# cSLIM-SA_RS485.net
KiCad netlist of a schematic drawn in Altium Designer
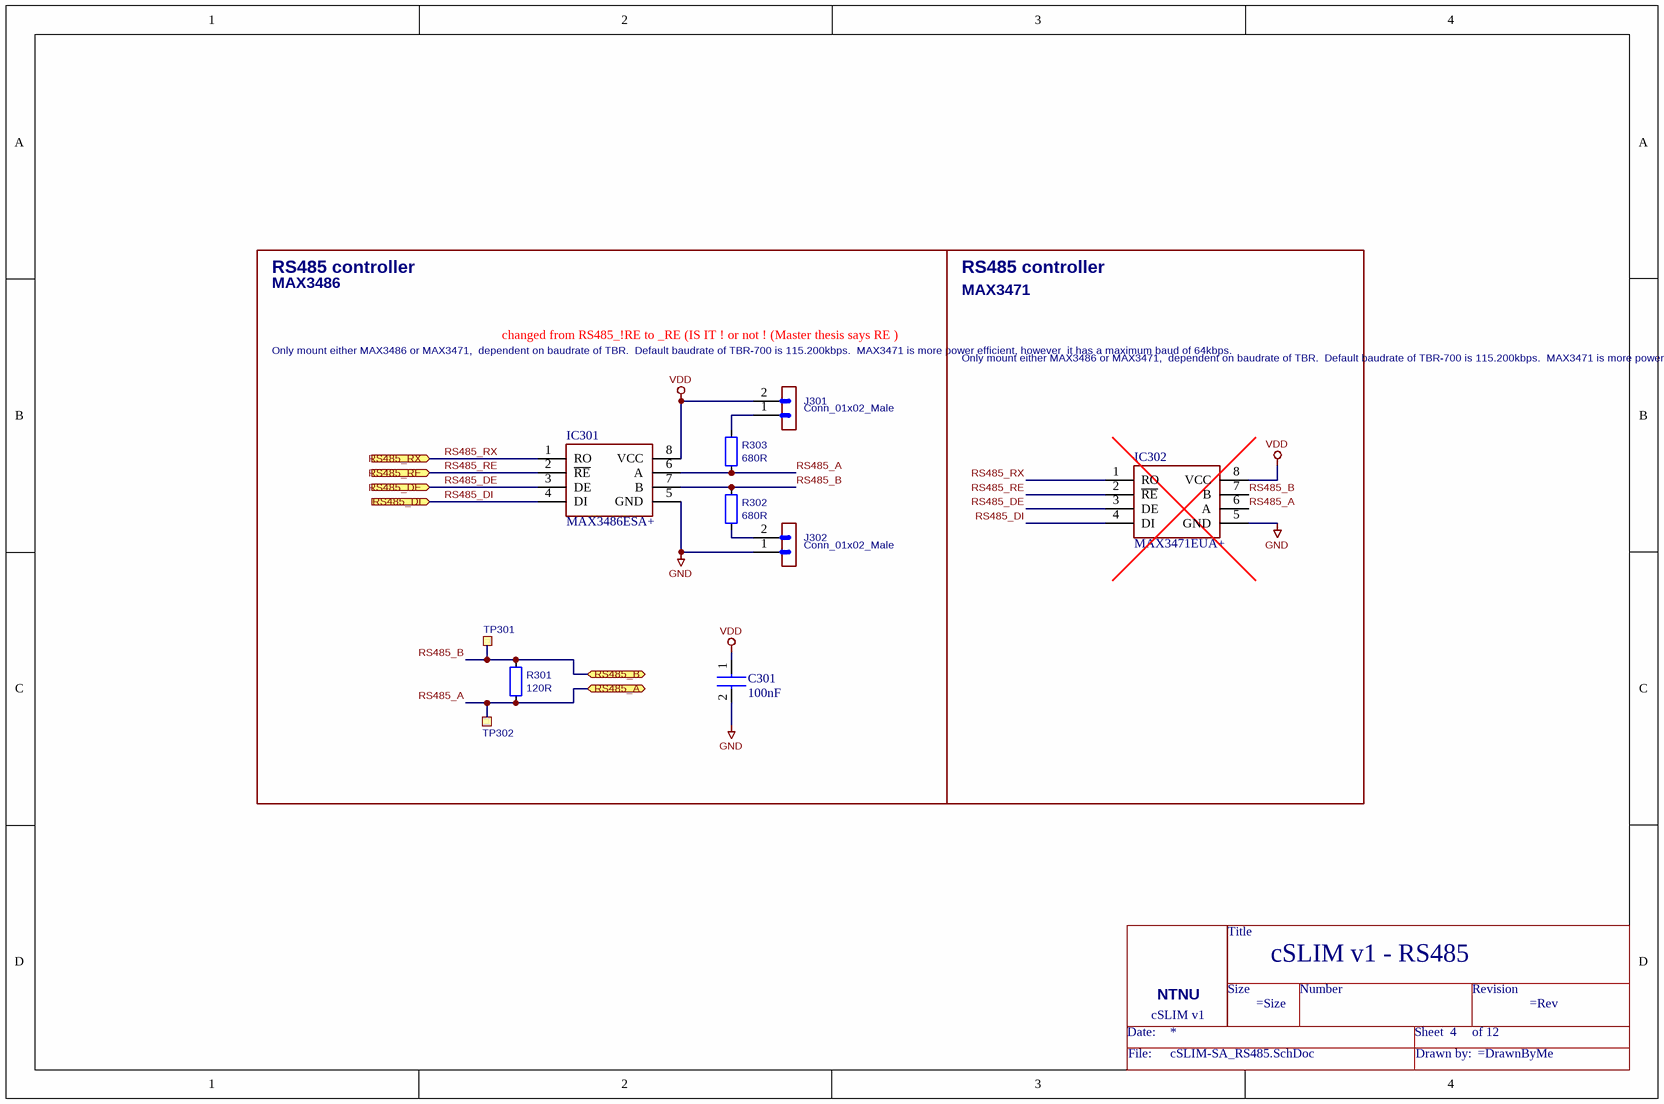
[diagram p0: cSLIM-SA_RS485.SchDoc]

(export (version "E")
  (design (tool "Eeschema 10.0.6"))
  (components
    (comp (ref "C301")
      (value "100nF")
      (footprint "cSLIM-SA:CAPC1608X90N")
      (description "Capacitor")
      (fields
        (field (name "MANUFACTURER_PART_NUMBER") "06033G104ZAT2A")
        (field (name "MOUSER PART NUMBER") "581-06033G104Z")
      )
      (libsource (lib "cSLIM-SA") (part "C"))
    )
    (comp (ref "IC301")
      (value "MAX3486ESA+")
      (footprint "cSLIM-SA:SOIC127P600X175-8N")
      (description "Integrated Circuit")
      (fields (field (name "MOUSER PART NUMBER") "700-MAX3486ESA"))
      (libsource (lib "cSLIM-SA") (part "MAX3486ESA+"))
    )
    (comp (ref "IC302")
      (value "MAX3471EUA+")
      (footprint "cSLIM-SA:SOP65P490X110-8N")
      (description "Integrated Circuit")
      (fields (field (name "MOUSER PART NUMBER") "700-MAX3471EUA"))
      (libsource (lib "cSLIM-SA") (part "MAX3471EUA+"))
    )
    (comp (ref "J301")
      (value "Conn_01x02_Male")
      (footprint "cSLIM-SA:HDRV2W110P0X254_1X2_508X254X854P")
      (description "Connector")
      (fields
        (field (name "MANUFACTURER_PART_NUMBER") "61300211121")
        (field (name "MOUSER PART NUMBER") "710-61300211121")
      )
      (libsource (lib "cSLIM-SA") (part "61300211121"))
    )
    (comp (ref "J302")
      (value "Conn_01x02_Male")
      (footprint "cSLIM-SA:HDRV2W110P0X254_1X2_508X254X854P")
      (description "Connector")
      (fields
        (field (name "MANUFACTURER_PART_NUMBER") "61300211121")
        (field (name "MOUSER PART NUMBER") "710-61300211121")
      )
      (libsource (lib "cSLIM-SA") (part "61300211121"))
    )
    (comp (ref "R301") (value "120R") (footprint "RESC1608X55N") (libsource (lib "cSLIM-SA") (part "R")))
    (comp (ref "R302") (value "680R") (footprint "RESC1608X55N") (libsource (lib "cSLIM-SA") (part "R")))
    (comp (ref "R303") (value "680R") (footprint "RESC1608X55N") (libsource (lib "cSLIM-SA") (part "R")))
    (comp (ref "TP301") (value "~") (footprint "cSLIM-SA:TP_SMD_Ø1.0mm") (libsource (lib "") (part "TP_1")))
    (comp (ref "TP302")
      (value "~")
      (footprint "cSLIM-SA:TP_SMD_Ø1.0mm")
      (libsource (lib "cSLIM-SA") (part "TP"))
    )
  )
  (nets
    (net (code "1") (name "/RS485_A") (class "Default")
      (node (ref "IC301") (pin "6") (pinfunction "A_6") (pintype "passive"))
      (node (ref "IC302") (pin "6") (pinfunction "A_6") (pintype "passive"))
      (node (ref "R301") (pin "2") (pinfunction "2_2") (pintype "passive"))
      (node (ref "R303") (pin "2") (pinfunction "2_2") (pintype "passive"))
      (node (ref "TP302") (pin "1") (pinfunction "1_1") (pintype "passive"))
    )
    (net (code "2") (name "/RS485_B") (class "Default")
      (node (ref "IC301") (pin "7") (pinfunction "B_7") (pintype "passive"))
      (node (ref "IC302") (pin "7") (pinfunction "B_7") (pintype "passive"))
      (node (ref "R301") (pin "1") (pinfunction "1_1") (pintype "passive"))
      (node (ref "R302") (pin "1") (pinfunction "1_1") (pintype "passive"))
      (node (ref "TP301") (pin "1") (pinfunction "1_1") (pintype "passive"))
    )
    (net (code "3") (name "/RS485_DE") (class "Default")
      (node (ref "IC301") (pin "3") (pinfunction "DE_3") (pintype "passive"))
      (node (ref "IC302") (pin "3") (pinfunction "DE_3") (pintype "passive"))
    )
    (net (code "4") (name "/RS485_DI") (class "Default")
      (node (ref "IC301") (pin "4") (pinfunction "DI_4") (pintype "passive"))
      (node (ref "IC302") (pin "4") (pinfunction "DI_4") (pintype "passive"))
    )
    (net (code "5") (name "/RS485_RE") (class "Default")
      (node (ref "IC301") (pin "2") (pinfunction "~{RE}_2") (pintype "passive"))
      (node (ref "IC302") (pin "2") (pinfunction "~{RE}_2") (pintype "passive"))
    )
    (net (code "6") (name "/RS485_RX") (class "Default")
      (node (ref "IC301") (pin "1") (pinfunction "RO_1") (pintype "passive"))
      (node (ref "IC302") (pin "1") (pinfunction "RO_1") (pintype "passive"))
    )
    (net (code "7") (name "GND") (class "Default")
      (node (ref "C301") (pin "2") (pinfunction "2_2") (pintype "passive"))
      (node (ref "IC301") (pin "5") (pinfunction "GND_5") (pintype "passive"))
      (node (ref "IC302") (pin "5") (pinfunction "GND_5") (pintype "passive"))
      (node (ref "J302") (pin "1") (pinfunction "1_1") (pintype "passive"))
    )
    (net (code "8") (name "Net-(J301-Pad1)") (class "Default")
      (node (ref "J301") (pin "1") (pinfunction "1_1") (pintype "passive"))
      (node (ref "R303") (pin "1") (pinfunction "1_1") (pintype "passive"))
    )
    (net (code "9") (name "Net-(J302-Pad2)") (class "Default")
      (node (ref "J302") (pin "2") (pinfunction "2_2") (pintype "passive"))
      (node (ref "R302") (pin "2") (pinfunction "2_2") (pintype "passive"))
    )
    (net (code "10") (name "VDD") (class "Default")
      (node (ref "C301") (pin "1") (pinfunction "1_1") (pintype "passive"))
      (node (ref "IC301") (pin "8") (pinfunction "VCC_8") (pintype "passive"))
      (node (ref "IC302") (pin "8") (pinfunction "VCC_8") (pintype "passive"))
      (node (ref "J301") (pin "2") (pinfunction "2_2") (pintype "passive"))
    )
  )
)
